# 19_SOLENOID_HB_1.net
KiCad netlist of a schematic drawn in Altium Designer
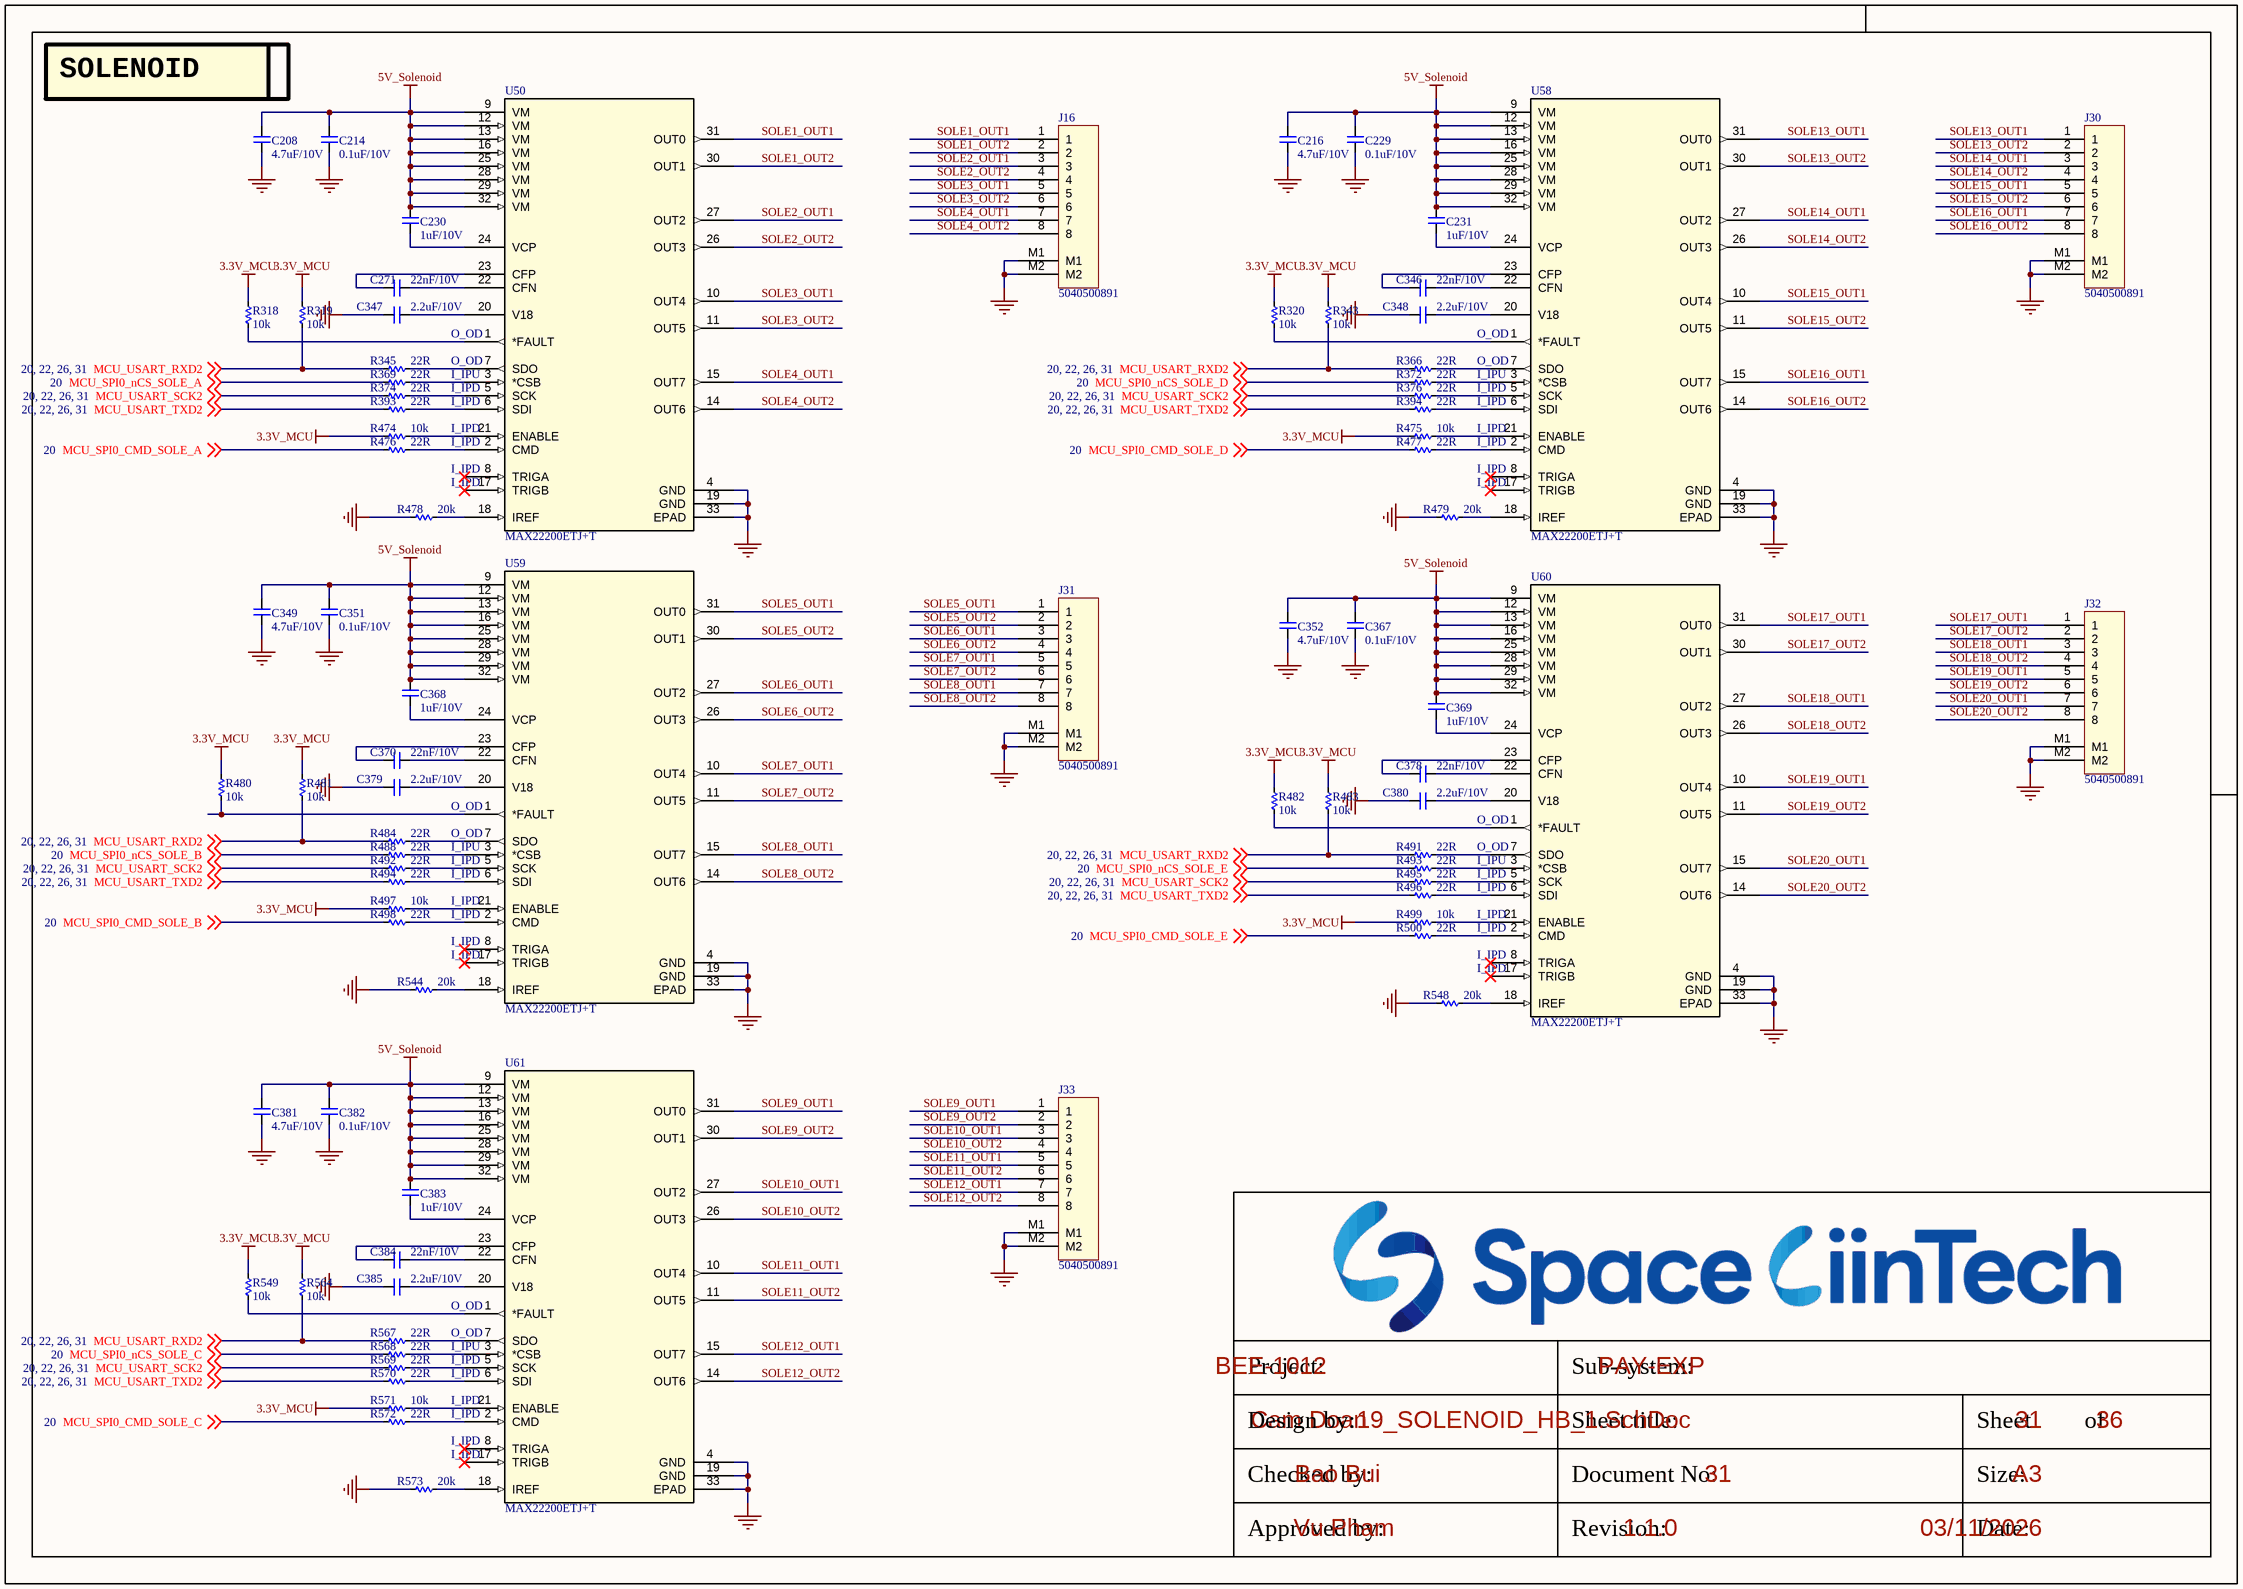
[diagram p0: 19_SOLENOID_HB_1.SchDoc]

(export (version "E")
  (design (tool "Eeschema 10.0.6"))
  (components
    (comp (ref "C208")
      (value "4.7uF/10V")
      (footprint "CAP_C_1005X60")
      (description "CAP CHIP")
      (libsource (lib "LABLIB") (part "_CAP_C_2"))
    )
    (comp (ref "C214")
      (value "0.1uF/10V")
      (footprint "CAP_C_1005X60")
      (description "CAP CHIP")
      (libsource (lib "LABLIB") (part "_CAP_C_2"))
    )
    (comp (ref "C216")
      (value "4.7uF/10V")
      (footprint "CAP_C_1005X60")
      (description "CAP CHIP")
      (libsource (lib "LABLIB") (part "_CAP_C_2"))
    )
    (comp (ref "C229")
      (value "0.1uF/10V")
      (footprint "CAP_C_1005X60")
      (description "CAP CHIP")
      (libsource (lib "LABLIB") (part "_CAP_C_2"))
    )
    (comp (ref "C230")
      (value "1uF/10V")
      (footprint "CAP_C_1005X60")
      (description "CAP CHIP")
      (libsource (lib "LABLIB") (part "_CAP_C_2"))
    )
    (comp (ref "C231")
      (value "1uF/10V")
      (footprint "CAP_C_1005X60")
      (description "CAP CHIP")
      (libsource (lib "LABLIB") (part "_CAP_C_2"))
    )
    (comp (ref "C271")
      (value "22nF/10V")
      (footprint "CAP_C_1005X60")
      (description "CAP CHIP")
      (libsource (lib "LABLIB") (part "_CAP_C_2"))
    )
    (comp (ref "C346")
      (value "22nF/10V")
      (footprint "CAP_C_1005X60")
      (description "CAP CHIP")
      (libsource (lib "LABLIB") (part "_CAP_C_2"))
    )
    (comp (ref "C347")
      (value "2.2uF/10V")
      (footprint "CAP_C_1005X60")
      (description "CAP CHIP")
      (libsource (lib "LABLIB") (part "_CAP_C_2"))
    )
    (comp (ref "C348")
      (value "2.2uF/10V")
      (footprint "CAP_C_1005X60")
      (description "CAP CHIP")
      (libsource (lib "LABLIB") (part "_CAP_C_2"))
    )
    (comp (ref "C349")
      (value "4.7uF/10V")
      (footprint "CAP_C_1005X60")
      (description "CAP CHIP")
      (libsource (lib "LABLIB") (part "_CAP_C_2"))
    )
    (comp (ref "C351")
      (value "0.1uF/10V")
      (footprint "CAP_C_1005X60")
      (description "CAP CHIP")
      (libsource (lib "LABLIB") (part "_CAP_C_2"))
    )
    (comp (ref "C352")
      (value "4.7uF/10V")
      (footprint "CAP_C_1005X60")
      (description "CAP CHIP")
      (libsource (lib "LABLIB") (part "_CAP_C_2"))
    )
    (comp (ref "C367")
      (value "0.1uF/10V")
      (footprint "CAP_C_1005X60")
      (description "CAP CHIP")
      (libsource (lib "LABLIB") (part "_CAP_C_2"))
    )
    (comp (ref "C368")
      (value "1uF/10V")
      (footprint "CAP_C_1005X60")
      (description "CAP CHIP")
      (libsource (lib "LABLIB") (part "_CAP_C_2"))
    )
    (comp (ref "C369")
      (value "1uF/10V")
      (footprint "CAP_C_1005X60")
      (description "CAP CHIP")
      (libsource (lib "LABLIB") (part "_CAP_C_2"))
    )
    (comp (ref "C370")
      (value "22nF/10V")
      (footprint "CAP_C_1005X60")
      (description "CAP CHIP")
      (libsource (lib "LABLIB") (part "_CAP_C_2"))
    )
    (comp (ref "C378")
      (value "22nF/10V")
      (footprint "CAP_C_1005X60")
      (description "CAP CHIP")
      (libsource (lib "LABLIB") (part "_CAP_C_2"))
    )
    (comp (ref "C379")
      (value "2.2uF/10V")
      (footprint "CAP_C_1005X60")
      (description "CAP CHIP")
      (libsource (lib "LABLIB") (part "_CAP_C_2"))
    )
    (comp (ref "C380")
      (value "2.2uF/10V")
      (footprint "CAP_C_1005X60")
      (description "CAP CHIP")
      (libsource (lib "LABLIB") (part "_CAP_C_2"))
    )
    (comp (ref "C381")
      (value "4.7uF/10V")
      (footprint "CAP_C_1005X60")
      (description "CAP CHIP")
      (libsource (lib "LABLIB") (part "_CAP_C_2"))
    )
    (comp (ref "C382")
      (value "0.1uF/10V")
      (footprint "CAP_C_1005X60")
      (description "CAP CHIP")
      (libsource (lib "LABLIB") (part "_CAP_C_2"))
    )
    (comp (ref "C383")
      (value "1uF/10V")
      (footprint "CAP_C_1005X60")
      (description "CAP CHIP")
      (libsource (lib "LABLIB") (part "_CAP_C_2"))
    )
    (comp (ref "C384")
      (value "22nF/10V")
      (footprint "CAP_C_1005X60")
      (description "CAP CHIP")
      (libsource (lib "LABLIB") (part "_CAP_C_2"))
    )
    (comp (ref "C385")
      (value "2.2uF/10V")
      (footprint "CAP_C_1005X60")
      (description "CAP CHIP")
      (libsource (lib "LABLIB") (part "_CAP_C_2"))
    )
    (comp (ref "J16")
      (value "5040500891")
      (footprint "MOLEX_5040500891")
      (libsource (lib "LABLIB") (part "Header 8x1_2M"))
    )
    (comp (ref "J30")
      (value "5040500891")
      (footprint "MOLEX_5040500891")
      (libsource (lib "LABLIB") (part "Header 8x1_2M"))
    )
    (comp (ref "J31")
      (value "5040500891")
      (footprint "MOLEX_5040500891")
      (libsource (lib "LABLIB") (part "Header 8x1_2M"))
    )
    (comp (ref "J32")
      (value "5040500891")
      (footprint "MOLEX_5040500891")
      (libsource (lib "LABLIB") (part "Header 8x1_2M"))
    )
    (comp (ref "J33")
      (value "5040500891")
      (footprint "MOLEX_5040500891")
      (libsource (lib "LABLIB") (part "Header 8x1_2M"))
    )
    (comp (ref "R318")
      (value "10k")
      (footprint "RES_C_1005X40")
      (description "RES")
      (libsource (lib "LABLIB") (part "_RES_B_2"))
    )
    (comp (ref "R319")
      (value "10k")
      (footprint "RES_C_1005X40")
      (description "RES")
      (libsource (lib "LABLIB") (part "_RES_B_2"))
    )
    (comp (ref "R320")
      (value "10k")
      (footprint "RES_C_1005X40")
      (description "RES")
      (libsource (lib "LABLIB") (part "_RES_B_2"))
    )
    (comp (ref "R343")
      (value "10k")
      (footprint "RES_C_1005X40")
      (description "RES")
      (libsource (lib "LABLIB") (part "_RES_B_2"))
    )
    (comp (ref "R345")
      (value "22R")
      (footprint "RES_C_1005X40")
      (description "RES")
      (libsource (lib "LABLIB") (part "_RES_B_2"))
    )
    (comp (ref "R366")
      (value "22R")
      (footprint "RES_C_1005X40")
      (description "RES")
      (libsource (lib "LABLIB") (part "_RES_B_2"))
    )
    (comp (ref "R369")
      (value "22R")
      (footprint "RES_C_1005X40")
      (description "RES")
      (libsource (lib "LABLIB") (part "_RES_B_2"))
    )
    (comp (ref "R372")
      (value "22R")
      (footprint "RES_C_1005X40")
      (description "RES")
      (libsource (lib "LABLIB") (part "_RES_B_2"))
    )
    (comp (ref "R374")
      (value "22R")
      (footprint "RES_C_1005X40")
      (description "RES")
      (libsource (lib "LABLIB") (part "_RES_B_2"))
    )
    (comp (ref "R376")
      (value "22R")
      (footprint "RES_C_1005X40")
      (description "RES")
      (libsource (lib "LABLIB") (part "_RES_B_2"))
    )
    (comp (ref "R393")
      (value "22R")
      (footprint "RES_C_1005X40")
      (description "RES")
      (libsource (lib "LABLIB") (part "_RES_B_2"))
    )
    (comp (ref "R394")
      (value "22R")
      (footprint "RES_C_1005X40")
      (description "RES")
      (libsource (lib "LABLIB") (part "_RES_B_2"))
    )
    (comp (ref "R474")
      (value "10k")
      (footprint "RES_C_1005X40")
      (description "RES")
      (libsource (lib "LABLIB") (part "_RES_B_2"))
    )
    (comp (ref "R475")
      (value "10k")
      (footprint "RES_C_1005X40")
      (description "RES")
      (libsource (lib "LABLIB") (part "_RES_B_2"))
    )
    (comp (ref "R476")
      (value "22R")
      (footprint "RES_C_1005X40")
      (description "RES")
      (libsource (lib "LABLIB") (part "_RES_B_2"))
    )
    (comp (ref "R477")
      (value "22R")
      (footprint "RES_C_1005X40")
      (description "RES")
      (libsource (lib "LABLIB") (part "_RES_B_2"))
    )
    (comp (ref "R478")
      (value "20k")
      (footprint "RES_C_1005X40")
      (description "RES")
      (libsource (lib "LABLIB") (part "_RES_B_2"))
    )
    (comp (ref "R479")
      (value "20k")
      (footprint "RES_C_1005X40")
      (description "RES")
      (libsource (lib "LABLIB") (part "_RES_B_2"))
    )
    (comp (ref "R480")
      (value "10k")
      (footprint "RES_C_1005X40")
      (description "RES")
      (libsource (lib "LABLIB") (part "_RES_B_2"))
    )
    (comp (ref "R481")
      (value "10k")
      (footprint "RES_C_1005X40")
      (description "RES")
      (libsource (lib "LABLIB") (part "_RES_B_2"))
    )
    (comp (ref "R482")
      (value "10k")
      (footprint "RES_C_1005X40")
      (description "RES")
      (libsource (lib "LABLIB") (part "_RES_B_2"))
    )
    (comp (ref "R483")
      (value "10k")
      (footprint "RES_C_1005X40")
      (description "RES")
      (libsource (lib "LABLIB") (part "_RES_B_2"))
    )
    (comp (ref "R484")
      (value "22R")
      (footprint "RES_C_1005X40")
      (description "RES")
      (libsource (lib "LABLIB") (part "_RES_B_2"))
    )
    (comp (ref "R488")
      (value "22R")
      (footprint "RES_C_1005X40")
      (description "RES")
      (libsource (lib "LABLIB") (part "_RES_B_2"))
    )
    (comp (ref "R491")
      (value "22R")
      (footprint "RES_C_1005X40")
      (description "RES")
      (libsource (lib "LABLIB") (part "_RES_B_2"))
    )
    (comp (ref "R492")
      (value "22R")
      (footprint "RES_C_1005X40")
      (description "RES")
      (libsource (lib "LABLIB") (part "_RES_B_2"))
    )
    (comp (ref "R493")
      (value "22R")
      (footprint "RES_C_1005X40")
      (description "RES")
      (libsource (lib "LABLIB") (part "_RES_B_2"))
    )
    (comp (ref "R494")
      (value "22R")
      (footprint "RES_C_1005X40")
      (description "RES")
      (libsource (lib "LABLIB") (part "_RES_B_2"))
    )
    (comp (ref "R495")
      (value "22R")
      (footprint "RES_C_1005X40")
      (description "RES")
      (libsource (lib "LABLIB") (part "_RES_B_2"))
    )
    (comp (ref "R496")
      (value "22R")
      (footprint "RES_C_1005X40")
      (description "RES")
      (libsource (lib "LABLIB") (part "_RES_B_2"))
    )
    (comp (ref "R497")
      (value "10k")
      (footprint "RES_C_1005X40")
      (description "RES")
      (libsource (lib "LABLIB") (part "_RES_B_2"))
    )
    (comp (ref "R498")
      (value "22R")
      (footprint "RES_C_1005X40")
      (description "RES")
      (libsource (lib "LABLIB") (part "_RES_B_2"))
    )
    (comp (ref "R499")
      (value "10k")
      (footprint "RES_C_1005X40")
      (description "RES")
      (libsource (lib "LABLIB") (part "_RES_B_2"))
    )
    (comp (ref "R500")
      (value "22R")
      (footprint "RES_C_1005X40")
      (description "RES")
      (libsource (lib "LABLIB") (part "_RES_B_2"))
    )
    (comp (ref "R544")
      (value "20k")
      (footprint "RES_C_1005X40")
      (description "RES")
      (libsource (lib "LABLIB") (part "_RES_B_2"))
    )
    (comp (ref "R548")
      (value "20k")
      (footprint "RES_C_1005X40")
      (description "RES")
      (libsource (lib "LABLIB") (part "_RES_B_2"))
    )
    (comp (ref "R549")
      (value "10k")
      (footprint "RES_C_1005X40")
      (description "RES")
      (libsource (lib "LABLIB") (part "_RES_B_2"))
    )
    (comp (ref "R564")
      (value "10k")
      (footprint "RES_C_1005X40")
      (description "RES")
      (libsource (lib "LABLIB") (part "_RES_B_2"))
    )
    (comp (ref "R567")
      (value "22R")
      (footprint "RES_C_1005X40")
      (description "RES")
      (libsource (lib "LABLIB") (part "_RES_B_2"))
    )
    (comp (ref "R568")
      (value "22R")
      (footprint "RES_C_1005X40")
      (description "RES")
      (libsource (lib "LABLIB") (part "_RES_B_2"))
    )
    (comp (ref "R569")
      (value "22R")
      (footprint "RES_C_1005X40")
      (description "RES")
      (libsource (lib "LABLIB") (part "_RES_B_2"))
    )
    (comp (ref "R570")
      (value "22R")
      (footprint "RES_C_1005X40")
      (description "RES")
      (libsource (lib "LABLIB") (part "_RES_B_2"))
    )
    (comp (ref "R571")
      (value "10k")
      (footprint "RES_C_1005X40")
      (description "RES")
      (libsource (lib "LABLIB") (part "_RES_B_2"))
    )
    (comp (ref "R572")
      (value "22R")
      (footprint "RES_C_1005X40")
      (description "RES")
      (libsource (lib "LABLIB") (part "_RES_B_2"))
    )
    (comp (ref "R573")
      (value "20k")
      (footprint "RES_C_1005X40")
      (description "RES")
      (libsource (lib "LABLIB") (part "_RES_B_2"))
    )
    (comp (ref "U50")
      (value "MAX22200ETJ+T")
      (footprint "21-0140AK_T3255_8C_MXM")
      (description "36V, 1A Octal Integrated Serial-Controlled Solenoid and Motor Driver")
      (fields (field (name "COPYRIGHT") "Copyright (C) 2026 Ultra Librarian. All rights reserved."))
      (libsource (lib "LABLIB") (part "MAX22200ETJ+T"))
    )
    (comp (ref "U58")
      (value "MAX22200ETJ+T")
      (footprint "21-0140AK_T3255_8C_MXM")
      (description "36V, 1A Octal Integrated Serial-Controlled Solenoid and Motor Driver")
      (fields (field (name "COPYRIGHT") "Copyright (C) 2026 Ultra Librarian. All rights reserved."))
      (libsource (lib "LABLIB") (part "MAX22200ETJ+T"))
    )
    (comp (ref "U59")
      (value "MAX22200ETJ+T")
      (footprint "21-0140AK_T3255_8C_MXM")
      (description "36V, 1A Octal Integrated Serial-Controlled Solenoid and Motor Driver")
      (fields (field (name "COPYRIGHT") "Copyright (C) 2026 Ultra Librarian. All rights reserved."))
      (libsource (lib "LABLIB") (part "MAX22200ETJ+T"))
    )
    (comp (ref "U60")
      (value "MAX22200ETJ+T")
      (footprint "21-0140AK_T3255_8C_MXM")
      (description "36V, 1A Octal Integrated Serial-Controlled Solenoid and Motor Driver")
      (fields (field (name "COPYRIGHT") "Copyright (C) 2026 Ultra Librarian. All rights reserved."))
      (libsource (lib "LABLIB") (part "MAX22200ETJ+T"))
    )
    (comp (ref "U61")
      (value "MAX22200ETJ+T")
      (footprint "21-0140AK_T3255_8C_MXM")
      (description "36V, 1A Octal Integrated Serial-Controlled Solenoid and Motor Driver")
      (fields (field (name "COPYRIGHT") "Copyright (C) 2026 Ultra Librarian. All rights reserved."))
      (libsource (lib "LABLIB") (part "MAX22200ETJ+T"))
    )
  )
  (nets
    (net (code "1") (name "/SOLE1_OUT1") (class "Default")
      (node (ref "J16") (pin "1") (pinfunction "1_1") (pintype "passive"))
      (node (ref "U50") (pin "31") (pinfunction "OUT0_31") (pintype "output"))
    )
    (net (code "2") (name "/SOLE1_OUT2") (class "Default")
      (node (ref "J16") (pin "2") (pinfunction "2_2") (pintype "passive"))
      (node (ref "U50") (pin "30") (pinfunction "OUT1_30") (pintype "output"))
    )
    (net (code "3") (name "/SOLE2_OUT1") (class "Default")
      (node (ref "J16") (pin "3") (pinfunction "3_3") (pintype "passive"))
      (node (ref "U50") (pin "27") (pinfunction "OUT2_27") (pintype "output"))
    )
    (net (code "4") (name "/SOLE2_OUT2") (class "Default")
      (node (ref "J16") (pin "4") (pinfunction "4_4") (pintype "passive"))
      (node (ref "U50") (pin "26") (pinfunction "OUT3_26") (pintype "output"))
    )
    (net (code "5") (name "/SOLE3_OUT1") (class "Default")
      (node (ref "J16") (pin "5") (pinfunction "5_5") (pintype "passive"))
      (node (ref "U50") (pin "10") (pinfunction "OUT4_10") (pintype "output"))
    )
    (net (code "6") (name "/SOLE3_OUT2") (class "Default")
      (node (ref "J16") (pin "6") (pinfunction "6_6") (pintype "passive"))
      (node (ref "U50") (pin "11") (pinfunction "OUT5_11") (pintype "output"))
    )
    (net (code "7") (name "/SOLE4_OUT1") (class "Default")
      (node (ref "J16") (pin "7") (pinfunction "7_7") (pintype "passive"))
      (node (ref "U50") (pin "15") (pinfunction "OUT7_15") (pintype "output"))
    )
    (net (code "8") (name "/SOLE4_OUT2") (class "Default")
      (node (ref "J16") (pin "8") (pinfunction "8_8") (pintype "passive"))
      (node (ref "U50") (pin "14") (pinfunction "OUT6_14") (pintype "output"))
    )
    (net (code "9") (name "/SOLE5_OUT1") (class "Default")
      (node (ref "J31") (pin "1") (pinfunction "1_1") (pintype "passive"))
      (node (ref "U59") (pin "31") (pinfunction "OUT0_31") (pintype "output"))
    )
    (net (code "10") (name "/SOLE5_OUT2") (class "Default")
      (node (ref "J31") (pin "2") (pinfunction "2_2") (pintype "passive"))
      (node (ref "U59") (pin "30") (pinfunction "OUT1_30") (pintype "output"))
    )
    (net (code "11") (name "/SOLE6_OUT1") (class "Default")
      (node (ref "J31") (pin "3") (pinfunction "3_3") (pintype "passive"))
      (node (ref "U59") (pin "27") (pinfunction "OUT2_27") (pintype "output"))
    )
    (net (code "12") (name "/SOLE6_OUT2") (class "Default")
      (node (ref "J31") (pin "4") (pinfunction "4_4") (pintype "passive"))
      (node (ref "U59") (pin "26") (pinfunction "OUT3_26") (pintype "output"))
    )
    (net (code "13") (name "/SOLE7_OUT1") (class "Default")
      (node (ref "J31") (pin "5") (pinfunction "5_5") (pintype "passive"))
      (node (ref "U59") (pin "10") (pinfunction "OUT4_10") (pintype "output"))
    )
    (net (code "14") (name "/SOLE7_OUT2") (class "Default")
      (node (ref "J31") (pin "6") (pinfunction "6_6") (pintype "passive"))
      (node (ref "U59") (pin "11") (pinfunction "OUT5_11") (pintype "output"))
    )
    (net (code "15") (name "/SOLE8_OUT1") (class "Default")
      (node (ref "J31") (pin "7") (pinfunction "7_7") (pintype "passive"))
      (node (ref "U59") (pin "15") (pinfunction "OUT7_15") (pintype "output"))
    )
    (net (code "16") (name "/SOLE8_OUT2") (class "Default")
      (node (ref "J31") (pin "8") (pinfunction "8_8") (pintype "passive"))
      (node (ref "U59") (pin "14") (pinfunction "OUT6_14") (pintype "output"))
    )
    (net (code "17") (name "/SOLE9_OUT1") (class "Default")
      (node (ref "J33") (pin "1") (pinfunction "1_1") (pintype "passive"))
      (node (ref "U61") (pin "31") (pinfunction "OUT0_31") (pintype "output"))
    )
    (net (code "18") (name "/SOLE9_OUT2") (class "Default")
      (node (ref "J33") (pin "2") (pinfunction "2_2") (pintype "passive"))
      (node (ref "U61") (pin "30") (pinfunction "OUT1_30") (pintype "output"))
    )
    (net (code "19") (name "/SOLE10_OUT1") (class "Default")
      (node (ref "J33") (pin "3") (pinfunction "3_3") (pintype "passive"))
      (node (ref "U61") (pin "27") (pinfunction "OUT2_27") (pintype "output"))
    )
    (net (code "20") (name "/SOLE10_OUT2") (class "Default")
      (node (ref "J33") (pin "4") (pinfunction "4_4") (pintype "passive"))
      (node (ref "U61") (pin "26") (pinfunction "OUT3_26") (pintype "output"))
    )
    (net (code "21") (name "/SOLE11_OUT1") (class "Default")
      (node (ref "J33") (pin "5") (pinfunction "5_5") (pintype "passive"))
      (node (ref "U61") (pin "10") (pinfunction "OUT4_10") (pintype "output"))
    )
    (net (code "22") (name "/SOLE11_OUT2") (class "Default")
      (node (ref "J33") (pin "6") (pinfunction "6_6") (pintype "passive"))
      (node (ref "U61") (pin "11") (pinfunction "OUT5_11") (pintype "output"))
    )
    (net (code "23") (name "/SOLE12_OUT1") (class "Default")
      (node (ref "J33") (pin "7") (pinfunction "7_7") (pintype "passive"))
      (node (ref "U61") (pin "15") (pinfunction "OUT7_15") (pintype "output"))
    )
    (net (code "24") (name "/SOLE12_OUT2") (class "Default")
      (node (ref "J33") (pin "8") (pinfunction "8_8") (pintype "passive"))
      (node (ref "U61") (pin "14") (pinfunction "OUT6_14") (pintype "output"))
    )
    (net (code "25") (name "/SOLE13_OUT1") (class "Default")
      (node (ref "J30") (pin "1") (pinfunction "1_1") (pintype "passive"))
      (node (ref "U58") (pin "31") (pinfunction "OUT0_31") (pintype "output"))
    )
    (net (code "26") (name "/SOLE13_OUT2") (class "Default")
      (node (ref "J30") (pin "2") (pinfunction "2_2") (pintype "passive"))
      (node (ref "U58") (pin "30") (pinfunction "OUT1_30") (pintype "output"))
    )
    (net (code "27") (name "/SOLE14_OUT1") (class "Default")
      (node (ref "J30") (pin "3") (pinfunction "3_3") (pintype "passive"))
      (node (ref "U58") (pin "27") (pinfunction "OUT2_27") (pintype "output"))
    )
    (net (code "28") (name "/SOLE14_OUT2") (class "Default")
      (node (ref "J30") (pin "4") (pinfunction "4_4") (pintype "passive"))
      (node (ref "U58") (pin "26") (pinfunction "OUT3_26") (pintype "output"))
    )
    (net (code "29") (name "/SOLE15_OUT1") (class "Default")
      (node (ref "J30") (pin "5") (pinfunction "5_5") (pintype "passive"))
      (node (ref "U58") (pin "10") (pinfunction "OUT4_10") (pintype "output"))
    )
    (net (code "30") (name "/SOLE15_OUT2") (class "Default")
      (node (ref "J30") (pin "6") (pinfunction "6_6") (pintype "passive"))
      (node (ref "U58") (pin "11") (pinfunction "OUT5_11") (pintype "output"))
    )
    (net (code "31") (name "/SOLE16_OUT1") (class "Default")
      (node (ref "J30") (pin "7") (pinfunction "7_7") (pintype "passive"))
      (node (ref "U58") (pin "15") (pinfunction "OUT7_15") (pintype "output"))
    )
    (net (code "32") (name "/SOLE16_OUT2") (class "Default")
      (node (ref "J30") (pin "8") (pinfunction "8_8") (pintype "passive"))
      (node (ref "U58") (pin "14") (pinfunction "OUT6_14") (pintype "output"))
    )
    (net (code "33") (name "/SOLE17_OUT1") (class "Default")
      (node (ref "J32") (pin "1") (pinfunction "1_1") (pintype "passive"))
      (node (ref "U60") (pin "31") (pinfunction "OUT0_31") (pintype "output"))
    )
    (net (code "34") (name "/SOLE17_OUT2") (class "Default")
      (node (ref "J32") (pin "2") (pinfunction "2_2") (pintype "passive"))
      (node (ref "U60") (pin "30") (pinfunction "OUT1_30") (pintype "output"))
    )
    (net (code "35") (name "/SOLE18_OUT1") (class "Default")
      (node (ref "J32") (pin "3") (pinfunction "3_3") (pintype "passive"))
      (node (ref "U60") (pin "27") (pinfunction "OUT2_27") (pintype "output"))
    )
    (net (code "36") (name "/SOLE18_OUT2") (class "Default")
      (node (ref "J32") (pin "4") (pinfunction "4_4") (pintype "passive"))
      (node (ref "U60") (pin "26") (pinfunction "OUT3_26") (pintype "output"))
    )
    (net (code "37") (name "/SOLE19_OUT1") (class "Default")
      (node (ref "J32") (pin "5") (pinfunction "5_5") (pintype "passive"))
      (node (ref "U60") (pin "10") (pinfunction "OUT4_10") (pintype "output"))
    )
    (net (code "38") (name "/SOLE19_OUT2") (class "Default")
      (node (ref "J32") (pin "6") (pinfunction "6_6") (pintype "passive"))
      (node (ref "U60") (pin "11") (pinfunction "OUT5_11") (pintype "output"))
    )
    (net (code "39") (name "/SOLE20_OUT1") (class "Default")
      (node (ref "J32") (pin "7") (pinfunction "7_7") (pintype "passive"))
      (node (ref "U60") (pin "15") (pinfunction "OUT7_15") (pintype "output"))
    )
    (net (code "40") (name "/SOLE20_OUT2") (class "Default")
      (node (ref "J32") (pin "8") (pinfunction "8_8") (pintype "passive"))
      (node (ref "U60") (pin "14") (pinfunction "OUT6_14") (pintype "output"))
    )
    (net (code "41") (name "3.3V_MCU") (class "Default")
      (node (ref "R318") (pin "1") (pinfunction "1_1") (pintype "passive"))
      (node (ref "R319") (pin "1") (pinfunction "1_1") (pintype "passive"))
      (node (ref "R320") (pin "1") (pinfunction "1_1") (pintype "passive"))
      (node (ref "R343") (pin "1") (pinfunction "1_1") (pintype "passive"))
      (node (ref "R474") (pin "1") (pinfunction "1_1") (pintype "passive"))
      (node (ref "R475") (pin "1") (pinfunction "1_1") (pintype "passive"))
      (node (ref "R480") (pin "1") (pinfunction "1_1") (pintype "passive"))
      (node (ref "R481") (pin "1") (pinfunction "1_1") (pintype "passive"))
      (node (ref "R482") (pin "1") (pinfunction "1_1") (pintype "passive"))
      (node (ref "R483") (pin "1") (pinfunction "1_1") (pintype "passive"))
      (node (ref "R497") (pin "1") (pinfunction "1_1") (pintype "passive"))
      (node (ref "R499") (pin "1") (pinfunction "1_1") (pintype "passive"))
      (node (ref "R549") (pin "1") (pinfunction "1_1") (pintype "passive"))
      (node (ref "R564") (pin "1") (pinfunction "1_1") (pintype "passive"))
      (node (ref "R571") (pin "1") (pinfunction "1_1") (pintype "passive"))
    )
    (net (code "42") (name "5V_Solenoid") (class "Default")
      (node (ref "C208") (pin "2") (pinfunction "2_2") (pintype "passive"))
      (node (ref "C214") (pin "2") (pinfunction "2_2") (pintype "passive"))
      (node (ref "C216") (pin "2") (pinfunction "2_2") (pintype "passive"))
      (node (ref "C229") (pin "2") (pinfunction "2_2") (pintype "passive"))
      (node (ref "C230") (pin "2") (pinfunction "2_2") (pintype "passive"))
      (node (ref "C231") (pin "2") (pinfunction "2_2") (pintype "passive"))
      (node (ref "C349") (pin "2") (pinfunction "2_2") (pintype "passive"))
      (node (ref "C351") (pin "2") (pinfunction "2_2") (pintype "passive"))
      (node (ref "C352") (pin "2") (pinfunction "2_2") (pintype "passive"))
      (node (ref "C367") (pin "2") (pinfunction "2_2") (pintype "passive"))
      (node (ref "C368") (pin "2") (pinfunction "2_2") (pintype "passive"))
      (node (ref "C369") (pin "2") (pinfunction "2_2") (pintype "passive"))
      (node (ref "C381") (pin "2") (pinfunction "2_2") (pintype "passive"))
      (node (ref "C382") (pin "2") (pinfunction "2_2") (pintype "passive"))
      (node (ref "C383") (pin "2") (pinfunction "2_2") (pintype "passive"))
      (node (ref "U50") (pin "12") (pinfunction "VM_12") (pintype "input"))
      (node (ref "U50") (pin "13") (pinfunction "VM_13") (pintype "input"))
      (node (ref "U50") (pin "16") (pinfunction "VM_16") (pintype "input"))
      (node (ref "U50") (pin "25") (pinfunction "VM_25") (pintype "input"))
      (node (ref "U50") (pin "28") (pinfunction "VM_28") (pintype "input"))
      (node (ref "U50") (pin "29") (pinfunction "VM_29") (pintype "input"))
      (node (ref "U50") (pin "32") (pinfunction "VM_32") (pintype "input"))
      (node (ref "U50") (pin "9") (pinfunction "VM_9") (pintype "power_in"))
      (node (ref "U58") (pin "12") (pinfunction "VM_12") (pintype "input"))
      (node (ref "U58") (pin "13") (pinfunction "VM_13") (pintype "input"))
      (node (ref "U58") (pin "16") (pinfunction "VM_16") (pintype "input"))
      (node (ref "U58") (pin "25") (pinfunction "VM_25") (pintype "input"))
      (node (ref "U58") (pin "28") (pinfunction "VM_28") (pintype "input"))
      (node (ref "U58") (pin "29") (pinfunction "VM_29") (pintype "input"))
      (node (ref "U58") (pin "32") (pinfunction "VM_32") (pintype "input"))
      (node (ref "U58") (pin "9") (pinfunction "VM_9") (pintype "power_in"))
      (node (ref "U59") (pin "12") (pinfunction "VM_12") (pintype "input"))
      (node (ref "U59") (pin "13") (pinfunction "VM_13") (pintype "input"))
      (node (ref "U59") (pin "16") (pinfunction "VM_16") (pintype "input"))
      (node (ref "U59") (pin "25") (pinfunction "VM_25") (pintype "input"))
      (node (ref "U59") (pin "28") (pinfunction "VM_28") (pintype "input"))
      (node (ref "U59") (pin "29") (pinfunction "VM_29") (pintype "input"))
      (node (ref "U59") (pin "32") (pinfunction "VM_32") (pintype "input"))
      (node (ref "U59") (pin "9") (pinfunction "VM_9") (pintype "power_in"))
      (node (ref "U60") (pin "12") (pinfunction "VM_12") (pintype "input"))
      (node (ref "U60") (pin "13") (pinfunction "VM_13") (pintype "input"))
      (node (ref "U60") (pin "16") (pinfunction "VM_16") (pintype "input"))
      (node (ref "U60") (pin "25") (pinfunction "VM_25") (pintype "input"))
      (node (ref "U60") (pin "28") (pinfunction "VM_28") (pintype "input"))
      (node (ref "U60") (pin "29") (pinfunction "VM_29") (pintype "input"))
      (node (ref "U60") (pin "32") (pinfunction "VM_32") (pintype "input"))
      (node (ref "U60") (pin "9") (pinfunction "VM_9") (pintype "power_in"))
      (node (ref "U61") (pin "12") (pinfunction "VM_12") (pintype "input"))
      (node (ref "U61") (pin "13") (pinfunction "VM_13") (pintype "input"))
      (node (ref "U61") (pin "16") (pinfunction "VM_16") (pintype "input"))
      (node (ref "U61") (pin "25") (pinfunction "VM_25") (pintype "input"))
      (node (ref "U61") (pin "28") (pinfunction "VM_28") (pintype "input"))
      (node (ref "U61") (pin "29") (pinfunction "VM_29") (pintype "input"))
      (node (ref "U61") (pin "32") (pinfunction "VM_32") (pintype "input"))
      (node (ref "U61") (pin "9") (pinfunction "VM_9") (pintype "power_in"))
    )
    (net (code "43") (name "GND") (class "Default")
      (node (ref "C208") (pin "1") (pinfunction "1_1") (pintype "passive"))
      (node (ref "C214") (pin "1") (pinfunction "1_1") (pintype "passive"))
      (node (ref "C216") (pin "1") (pinfunction "1_1") (pintype "passive"))
      (node (ref "C229") (pin "1") (pinfunction "1_1") (pintype "passive"))
      (node (ref "C347") (pin "1") (pinfunction "1_1") (pintype "passive"))
      (node (ref "C348") (pin "1") (pinfunction "1_1") (pintype "passive"))
      (node (ref "C349") (pin "1") (pinfunction "1_1") (pintype "passive"))
      (node (ref "C351") (pin "1") (pinfunction "1_1") (pintype "passive"))
      (node (ref "C352") (pin "1") (pinfunction "1_1") (pintype "passive"))
      (node (ref "C367") (pin "1") (pinfunction "1_1") (pintype "passive"))
      (node (ref "C379") (pin "1") (pinfunction "1_1") (pintype "passive"))
      (node (ref "C380") (pin "1") (pinfunction "1_1") (pintype "passive"))
      (node (ref "C381") (pin "1") (pinfunction "1_1") (pintype "passive"))
      (node (ref "C382") (pin "1") (pinfunction "1_1") (pintype "passive"))
      (node (ref "C385") (pin "1") (pinfunction "1_1") (pintype "passive"))
      (node (ref "J16") (pin "M1") (pinfunction "M1_M1") (pintype "passive"))
      (node (ref "J16") (pin "M2") (pinfunction "M2_M2") (pintype "passive"))
      (node (ref "J30") (pin "M1") (pinfunction "M1_M1") (pintype "passive"))
      (node (ref "J30") (pin "M2") (pinfunction "M2_M2") (pintype "passive"))
      (node (ref "J31") (pin "M1") (pinfunction "M1_M1") (pintype "passive"))
      (node (ref "J31") (pin "M2") (pinfunction "M2_M2") (pintype "passive"))
      (node (ref "J32") (pin "M1") (pinfunction "M1_M1") (pintype "passive"))
      (node (ref "J32") (pin "M2") (pinfunction "M2_M2") (pintype "passive"))
      (node (ref "J33") (pin "M1") (pinfunction "M1_M1") (pintype "passive"))
      (node (ref "J33") (pin "M2") (pinfunction "M2_M2") (pintype "passive"))
      (node (ref "R478") (pin "1") (pinfunction "1_1") (pintype "passive"))
      (node (ref "R479") (pin "1") (pinfunction "1_1") (pintype "passive"))
      (node (ref "R544") (pin "1") (pinfunction "1_1") (pintype "passive"))
      (node (ref "R548") (pin "1") (pinfunction "1_1") (pintype "passive"))
      (node (ref "R573") (pin "1") (pinfunction "1_1") (pintype "passive"))
      (node (ref "U50") (pin "19") (pinfunction "GND_19") (pintype "power_in"))
      (node (ref "U50") (pin "33") (pinfunction "EPAD_33") (pintype "power_in"))
      (node (ref "U50") (pin "4") (pinfunction "GND_4") (pintype "power_in"))
      (node (ref "U58") (pin "19") (pinfunction "GND_19") (pintype "power_in"))
      (node (ref "U58") (pin "33") (pinfunction "EPAD_33") (pintype "power_in"))
      (node (ref "U58") (pin "4") (pinfunction "GND_4") (pintype "power_in"))
      (node (ref "U59") (pin "19") (pinfunction "GND_19") (pintype "power_in"))
      (node (ref "U59") (pin "33") (pinfunction "EPAD_33") (pintype "power_in"))
      (node (ref "U59") (pin "4") (pinfunction "GND_4") (pintype "power_in"))
      (node (ref "U60") (pin "19") (pinfunction "GND_19") (pintype "power_in"))
      (node (ref "U60") (pin "33") (pinfunction "EPAD_33") (pintype "power_in"))
      (node (ref "U60") (pin "4") (pinfunction "GND_4") (pintype "power_in"))
      (node (ref "U61") (pin "19") (pinfunction "GND_19") (pintype "power_in"))
      (node (ref "U61") (pin "33") (pinfunction "EPAD_33") (pintype "power_in"))
      (node (ref "U61") (pin "4") (pinfunction "GND_4") (pintype "power_in"))
    )
    (net (code "44") (name "MCU_SPI0_CMD_SOLE_A") (class "Default")
      (node (ref "R476") (pin "1") (pinfunction "1_1") (pintype "passive"))
    )
    (net (code "45") (name "MCU_SPI0_CMD_SOLE_B") (class "Default")
      (node (ref "R498") (pin "1") (pinfunction "1_1") (pintype "passive"))
    )
    (net (code "46") (name "MCU_SPI0_CMD_SOLE_C") (class "Default")
      (node (ref "R572") (pin "1") (pinfunction "1_1") (pintype "passive"))
    )
    (net (code "47") (name "MCU_SPI0_CMD_SOLE_D") (class "Default")
      (node (ref "R477") (pin "1") (pinfunction "1_1") (pintype "passive"))
    )
    (net (code "48") (name "MCU_SPI0_CMD_SOLE_E") (class "Default")
      (node (ref "R500") (pin "1") (pinfunction "1_1") (pintype "passive"))
    )
    (net (code "49") (name "MCU_SPI0_nCS_SOLE_A") (class "Default")
      (node (ref "R369") (pin "1") (pinfunction "1_1") (pintype "passive"))
    )
    (net (code "50") (name "MCU_SPI0_nCS_SOLE_B") (class "Default")
      (node (ref "R488") (pin "1") (pinfunction "1_1") (pintype "passive"))
    )
    (net (code "51") (name "MCU_SPI0_nCS_SOLE_C") (class "Default")
      (node (ref "R568") (pin "1") (pinfunction "1_1") (pintype "passive"))
    )
    (net (code "52") (name "MCU_SPI0_nCS_SOLE_D") (class "Default")
      (node (ref "R372") (pin "1") (pinfunction "1_1") (pintype "passive"))
    )
    (net (code "53") (name "MCU_SPI0_nCS_SOLE_E") (class "Default")
      (node (ref "R493") (pin "1") (pinfunction "1_1") (pintype "passive"))
    )
    (net (code "54") (name "MCU_USART_RXD2") (class "Default")
      (node (ref "R319") (pin "2") (pinfunction "2_2") (pintype "passive"))
      (node (ref "R343") (pin "2") (pinfunction "2_2") (pintype "passive"))
      (node (ref "R345") (pin "1") (pinfunction "1_1") (pintype "passive"))
      (node (ref "R366") (pin "1") (pinfunction "1_1") (pintype "passive"))
      (node (ref "R481") (pin "2") (pinfunction "2_2") (pintype "passive"))
      (node (ref "R483") (pin "2") (pinfunction "2_2") (pintype "passive"))
      (node (ref "R484") (pin "1") (pinfunction "1_1") (pintype "passive"))
      (node (ref "R491") (pin "1") (pinfunction "1_1") (pintype "passive"))
      (node (ref "R564") (pin "2") (pinfunction "2_2") (pintype "passive"))
      (node (ref "R567") (pin "1") (pinfunction "1_1") (pintype "passive"))
    )
    (net (code "55") (name "MCU_USART_SCK2") (class "Default")
      (node (ref "R374") (pin "1") (pinfunction "1_1") (pintype "passive"))
      (node (ref "R376") (pin "1") (pinfunction "1_1") (pintype "passive"))
      (node (ref "R492") (pin "1") (pinfunction "1_1") (pintype "passive"))
      (node (ref "R495") (pin "1") (pinfunction "1_1") (pintype "passive"))
      (node (ref "R569") (pin "1") (pinfunction "1_1") (pintype "passive"))
    )
    (net (code "56") (name "MCU_USART_TXD2") (class "Default")
      (node (ref "R393") (pin "1") (pinfunction "1_1") (pintype "passive"))
      (node (ref "R394") (pin "1") (pinfunction "1_1") (pintype "passive"))
      (node (ref "R494") (pin "1") (pinfunction "1_1") (pintype "passive"))
      (node (ref "R496") (pin "1") (pinfunction "1_1") (pintype "passive"))
      (node (ref "R570") (pin "1") (pinfunction "1_1") (pintype "passive"))
    )
    (net (code "57") (name "Net-(U50-*CSB)") (class "Default")
      (node (ref "R369") (pin "2") (pinfunction "2_2") (pintype "passive"))
      (node (ref "U50") (pin "3") (pinfunction "*CSB_3") (pintype "input"))
    )
    (net (code "58") (name "Net-(U50-*FAULT)") (class "Default")
      (node (ref "R318") (pin "2") (pinfunction "2_2") (pintype "passive"))
      (node (ref "U50") (pin "1") (pinfunction "*FAULT_1") (pintype "output"))
    )
    (net (code "59") (name "Net-(U50-CFN)") (class "Default")
      (node (ref "C271") (pin "1") (pinfunction "1_1") (pintype "passive"))
      (node (ref "U50") (pin "22") (pinfunction "CFN_22") (pintype "power_in"))
    )
    (net (code "60") (name "Net-(U50-CFP)") (class "Default")
      (node (ref "C271") (pin "2") (pinfunction "2_2") (pintype "passive"))
      (node (ref "U50") (pin "23") (pinfunction "CFP_23") (pintype "power_in"))
    )
    (net (code "61") (name "Net-(U50-CMD)") (class "Default")
      (node (ref "R476") (pin "2") (pinfunction "2_2") (pintype "passive"))
      (node (ref "U50") (pin "2") (pinfunction "CMD_2") (pintype "input"))
    )
    (net (code "62") (name "Net-(U50-ENABLE)") (class "Default")
      (node (ref "R474") (pin "2") (pinfunction "2_2") (pintype "passive"))
      (node (ref "U50") (pin "21") (pinfunction "ENABLE_21") (pintype "input"))
    )
    (net (code "63") (name "Net-(U50-IREF)") (class "Default")
      (node (ref "R478") (pin "2") (pinfunction "2_2") (pintype "passive"))
      (node (ref "U50") (pin "18") (pinfunction "IREF_18") (pintype "input"))
    )
    (net (code "64") (name "Net-(U50-SCK)") (class "Default")
      (node (ref "R374") (pin "2") (pinfunction "2_2") (pintype "passive"))
      (node (ref "U50") (pin "5") (pinfunction "SCK_5") (pintype "input"))
    )
    (net (code "65") (name "Net-(U50-SDI)") (class "Default")
      (node (ref "R393") (pin "2") (pinfunction "2_2") (pintype "passive"))
      (node (ref "U50") (pin "6") (pinfunction "SDI_6") (pintype "input"))
    )
    (net (code "66") (name "Net-(U50-SDO)") (class "Default")
      (node (ref "R345") (pin "2") (pinfunction "2_2") (pintype "passive"))
      (node (ref "U50") (pin "7") (pinfunction "SDO_7") (pintype "output"))
    )
    (net (code "67") (name "Net-(U50-V18)") (class "Default")
      (node (ref "C347") (pin "2") (pinfunction "2_2") (pintype "passive"))
      (node (ref "U50") (pin "20") (pinfunction "V18_20") (pintype "power_in"))
    )
    (net (code "68") (name "Net-(U50-VCP)") (class "Default")
      (node (ref "C230") (pin "1") (pinfunction "1_1") (pintype "passive"))
      (node (ref "U50") (pin "24") (pinfunction "VCP_24") (pintype "power_in"))
    )
    (net (code "69") (name "Net-(U58-*CSB)") (class "Default")
      (node (ref "R372") (pin "2") (pinfunction "2_2") (pintype "passive"))
      (node (ref "U58") (pin "3") (pinfunction "*CSB_3") (pintype "input"))
    )
    (net (code "70") (name "Net-(U58-*FAULT)") (class "Default")
      (node (ref "R320") (pin "2") (pinfunction "2_2") (pintype "passive"))
      (node (ref "U58") (pin "1") (pinfunction "*FAULT_1") (pintype "output"))
    )
    (net (code "71") (name "Net-(U58-CFN)") (class "Default")
      (node (ref "C346") (pin "1") (pinfunction "1_1") (pintype "passive"))
      (node (ref "U58") (pin "22") (pinfunction "CFN_22") (pintype "power_in"))
    )
    (net (code "72") (name "Net-(U58-CFP)") (class "Default")
      (node (ref "C346") (pin "2") (pinfunction "2_2") (pintype "passive"))
      (node (ref "U58") (pin "23") (pinfunction "CFP_23") (pintype "power_in"))
    )
    (net (code "73") (name "Net-(U58-CMD)") (class "Default")
      (node (ref "R477") (pin "2") (pinfunction "2_2") (pintype "passive"))
      (node (ref "U58") (pin "2") (pinfunction "CMD_2") (pintype "input"))
    )
    (net (code "74") (name "Net-(U58-ENABLE)") (class "Default")
      (node (ref "R475") (pin "2") (pinfunction "2_2") (pintype "passive"))
      (node (ref "U58") (pin "21") (pinfunction "ENABLE_21") (pintype "input"))
    )
    (net (code "75") (name "Net-(U58-IREF)") (class "Default")
      (node (ref "R479") (pin "2") (pinfunction "2_2") (pintype "passive"))
      (node (ref "U58") (pin "18") (pinfunction "IREF_18") (pintype "input"))
    )
    (net (code "76") (name "Net-(U58-SCK)") (class "Default")
      (node (ref "R376") (pin "2") (pinfunction "2_2") (pintype "passive"))
      (node (ref "U58") (pin "5") (pinfunction "SCK_5") (pintype "input"))
    )
    (net (code "77") (name "Net-(U58-SDI)") (class "Default")
      (node (ref "R394") (pin "2") (pinfunction "2_2") (pintype "passive"))
      (node (ref "U58") (pin "6") (pinfunction "SDI_6") (pintype "input"))
    )
    (net (code "78") (name "Net-(U58-SDO)") (class "Default")
      (node (ref "R366") (pin "2") (pinfunction "2_2") (pintype "passive"))
      (node (ref "U58") (pin "7") (pinfunction "SDO_7") (pintype "output"))
    )
    (net (code "79") (name "Net-(U58-V18)") (class "Default")
      (node (ref "C348") (pin "2") (pinfunction "2_2") (pintype "passive"))
      (node (ref "U58") (pin "20") (pinfunction "V18_20") (pintype "power_in"))
    )
    (net (code "80") (name "Net-(U58-VCP)") (class "Default")
      (node (ref "C231") (pin "1") (pinfunction "1_1") (pintype "passive"))
      (node (ref "U58") (pin "24") (pinfunction "VCP_24") (pintype "power_in"))
    )
    (net (code "81") (name "Net-(U59-*CSB)") (class "Default")
      (node (ref "R488") (pin "2") (pinfunction "2_2") (pintype "passive"))
      (node (ref "U59") (pin "3") (pinfunction "*CSB_3") (pintype "input"))
    )
    (net (code "82") (name "Net-(U59-*FAULT)") (class "Default")
      (node (ref "R480") (pin "2") (pinfunction "2_2") (pintype "passive"))
      (node (ref "U59") (pin "1") (pinfunction "*FAULT_1") (pintype "output"))
    )
    (net (code "83") (name "Net-(U59-CFN)") (class "Default")
      (node (ref "C370") (pin "1") (pinfunction "1_1") (pintype "passive"))
      (node (ref "U59") (pin "22") (pinfunction "CFN_22") (pintype "power_in"))
    )
    (net (code "84") (name "Net-(U59-CFP)") (class "Default")
      (node (ref "C370") (pin "2") (pinfunction "2_2") (pintype "passive"))
      (node (ref "U59") (pin "23") (pinfunction "CFP_23") (pintype "power_in"))
    )
    (net (code "85") (name "Net-(U59-CMD)") (class "Default")
      (node (ref "R498") (pin "2") (pinfunction "2_2") (pintype "passive"))
      (node (ref "U59") (pin "2") (pinfunction "CMD_2") (pintype "input"))
    )
    (net (code "86") (name "Net-(U59-ENABLE)") (class "Default")
      (node (ref "R497") (pin "2") (pinfunction "2_2") (pintype "passive"))
      (node (ref "U59") (pin "21") (pinfunction "ENABLE_21") (pintype "input"))
    )
    (net (code "87") (name "Net-(U59-IREF)") (class "Default")
      (node (ref "R544") (pin "2") (pinfunction "2_2") (pintype "passive"))
      (node (ref "U59") (pin "18") (pinfunction "IREF_18") (pintype "input"))
    )
    (net (code "88") (name "Net-(U59-SCK)") (class "Default")
      (node (ref "R492") (pin "2") (pinfunction "2_2") (pintype "passive"))
      (node (ref "U59") (pin "5") (pinfunction "SCK_5") (pintype "input"))
    )
    (net (code "89") (name "Net-(U59-SDI)") (class "Default")
      (node (ref "R494") (pin "2") (pinfunction "2_2") (pintype "passive"))
      (node (ref "U59") (pin "6") (pinfunction "SDI_6") (pintype "input"))
    )
    (net (code "90") (name "Net-(U59-SDO)") (class "Default")
      (node (ref "R484") (pin "2") (pinfunction "2_2") (pintype "passive"))
      (node (ref "U59") (pin "7") (pinfunction "SDO_7") (pintype "output"))
    )
    (net (code "91") (name "Net-(U59-V18)") (class "Default")
      (node (ref "C379") (pin "2") (pinfunction "2_2") (pintype "passive"))
      (node (ref "U59") (pin "20") (pinfunction "V18_20") (pintype "power_in"))
    )
    (net (code "92") (name "Net-(U59-VCP)") (class "Default")
      (node (ref "C368") (pin "1") (pinfunction "1_1") (pintype "passive"))
      (node (ref "U59") (pin "24") (pinfunction "VCP_24") (pintype "power_in"))
    )
    (net (code "93") (name "Net-(U60-*CSB)") (class "Default")
      (node (ref "R493") (pin "2") (pinfunction "2_2") (pintype "passive"))
      (node (ref "U60") (pin "3") (pinfunction "*CSB_3") (pintype "input"))
    )
    (net (code "94") (name "Net-(U60-*FAULT)") (class "Default")
      (node (ref "R482") (pin "2") (pinfunction "2_2") (pintype "passive"))
      (node (ref "U60") (pin "1") (pinfunction "*FAULT_1") (pintype "output"))
    )
    (net (code "95") (name "Net-(U60-CFN)") (class "Default")
      (node (ref "C378") (pin "1") (pinfunction "1_1") (pintype "passive"))
      (node (ref "U60") (pin "22") (pinfunction "CFN_22") (pintype "power_in"))
    )
    (net (code "96") (name "Net-(U60-CFP)") (class "Default")
      (node (ref "C378") (pin "2") (pinfunction "2_2") (pintype "passive"))
      (node (ref "U60") (pin "23") (pinfunction "CFP_23") (pintype "power_in"))
    )
    (net (code "97") (name "Net-(U60-CMD)") (class "Default")
      (node (ref "R500") (pin "2") (pinfunction "2_2") (pintype "passive"))
      (node (ref "U60") (pin "2") (pinfunction "CMD_2") (pintype "input"))
    )
    (net (code "98") (name "Net-(U60-ENABLE)") (class "Default")
      (node (ref "R499") (pin "2") (pinfunction "2_2") (pintype "passive"))
      (node (ref "U60") (pin "21") (pinfunction "ENABLE_21") (pintype "input"))
    )
    (net (code "99") (name "Net-(U60-IREF)") (class "Default")
      (node (ref "R548") (pin "2") (pinfunction "2_2") (pintype "passive"))
      (node (ref "U60") (pin "18") (pinfunction "IREF_18") (pintype "input"))
    )
    (net (code "100") (name "Net-(U60-SCK)") (class "Default")
      (node (ref "R495") (pin "2") (pinfunction "2_2") (pintype "passive"))
      (node (ref "U60") (pin "5") (pinfunction "SCK_5") (pintype "input"))
    )
    (net (code "101") (name "Net-(U60-SDI)") (class "Default")
      (node (ref "R496") (pin "2") (pinfunction "2_2") (pintype "passive"))
      (node (ref "U60") (pin "6") (pinfunction "SDI_6") (pintype "input"))
    )
    (net (code "102") (name "Net-(U60-SDO)") (class "Default")
      (node (ref "R491") (pin "2") (pinfunction "2_2") (pintype "passive"))
      (node (ref "U60") (pin "7") (pinfunction "SDO_7") (pintype "output"))
    )
    (net (code "103") (name "Net-(U60-V18)") (class "Default")
      (node (ref "C380") (pin "2") (pinfunction "2_2") (pintype "passive"))
      (node (ref "U60") (pin "20") (pinfunction "V18_20") (pintype "power_in"))
    )
    (net (code "104") (name "Net-(U60-VCP)") (class "Default")
      (node (ref "C369") (pin "1") (pinfunction "1_1") (pintype "passive"))
      (node (ref "U60") (pin "24") (pinfunction "VCP_24") (pintype "power_in"))
    )
    (net (code "105") (name "Net-(U61-*CSB)") (class "Default")
      (node (ref "R568") (pin "2") (pinfunction "2_2") (pintype "passive"))
      (node (ref "U61") (pin "3") (pinfunction "*CSB_3") (pintype "input"))
    )
    (net (code "106") (name "Net-(U61-*FAULT)") (class "Default")
      (node (ref "R549") (pin "2") (pinfunction "2_2") (pintype "passive"))
      (node (ref "U61") (pin "1") (pinfunction "*FAULT_1") (pintype "output"))
    )
    (net (code "107") (name "Net-(U61-CFN)") (class "Default")
      (node (ref "C384") (pin "1") (pinfunction "1_1") (pintype "passive"))
      (node (ref "U61") (pin "22") (pinfunction "CFN_22") (pintype "power_in"))
    )
    (net (code "108") (name "Net-(U61-CFP)") (class "Default")
      (node (ref "C384") (pin "2") (pinfunction "2_2") (pintype "passive"))
      (node (ref "U61") (pin "23") (pinfunction "CFP_23") (pintype "power_in"))
    )
    (net (code "109") (name "Net-(U61-CMD)") (class "Default")
      (node (ref "R572") (pin "2") (pinfunction "2_2") (pintype "passive"))
      (node (ref "U61") (pin "2") (pinfunction "CMD_2") (pintype "input"))
    )
    (net (code "110") (name "Net-(U61-ENABLE)") (class "Default")
      (node (ref "R571") (pin "2") (pinfunction "2_2") (pintype "passive"))
      (node (ref "U61") (pin "21") (pinfunction "ENABLE_21") (pintype "input"))
    )
    (net (code "111") (name "Net-(U61-IREF)") (class "Default")
      (node (ref "R573") (pin "2") (pinfunction "2_2") (pintype "passive"))
      (node (ref "U61") (pin "18") (pinfunction "IREF_18") (pintype "input"))
    )
    (net (code "112") (name "Net-(U61-SCK)") (class "Default")
      (node (ref "R569") (pin "2") (pinfunction "2_2") (pintype "passive"))
      (node (ref "U61") (pin "5") (pinfunction "SCK_5") (pintype "input"))
    )
    (net (code "113") (name "Net-(U61-SDI)") (class "Default")
      (node (ref "R570") (pin "2") (pinfunction "2_2") (pintype "passive"))
      (node (ref "U61") (pin "6") (pinfunction "SDI_6") (pintype "input"))
    )
    (net (code "114") (name "Net-(U61-SDO)") (class "Default")
      (node (ref "R567") (pin "2") (pinfunction "2_2") (pintype "passive"))
      (node (ref "U61") (pin "7") (pinfunction "SDO_7") (pintype "output"))
    )
    (net (code "115") (name "Net-(U61-V18)") (class "Default")
      (node (ref "C385") (pin "2") (pinfunction "2_2") (pintype "passive"))
      (node (ref "U61") (pin "20") (pinfunction "V18_20") (pintype "power_in"))
    )
    (net (code "116") (name "Net-(U61-VCP)") (class "Default")
      (node (ref "C383") (pin "1") (pinfunction "1_1") (pintype "passive"))
      (node (ref "U61") (pin "24") (pinfunction "VCP_24") (pintype "power_in"))
    )
    (net (code "117") (name "unconnected-(U50-TRIGA-Pad8)") (class "Default")
      (node (ref "U50") (pin "8") (pinfunction "TRIGA_8") (pintype "input+no_connect"))
    )
    (net (code "118") (name "unconnected-(U50-TRIGB-Pad17)") (class "Default")
      (node (ref "U50") (pin "17") (pinfunction "TRIGB_17") (pintype "input+no_connect"))
    )
    (net (code "119") (name "unconnected-(U58-TRIGA-Pad8)") (class "Default")
      (node (ref "U58") (pin "8") (pinfunction "TRIGA_8") (pintype "input+no_connect"))
    )
    (net (code "120") (name "unconnected-(U58-TRIGB-Pad17)") (class "Default")
      (node (ref "U58") (pin "17") (pinfunction "TRIGB_17") (pintype "input+no_connect"))
    )
    (net (code "121") (name "unconnected-(U59-TRIGA-Pad8)") (class "Default")
      (node (ref "U59") (pin "8") (pinfunction "TRIGA_8") (pintype "input+no_connect"))
    )
    (net (code "122") (name "unconnected-(U59-TRIGB-Pad17)") (class "Default")
      (node (ref "U59") (pin "17") (pinfunction "TRIGB_17") (pintype "input+no_connect"))
    )
    (net (code "123") (name "unconnected-(U60-TRIGA-Pad8)") (class "Default")
      (node (ref "U60") (pin "8") (pinfunction "TRIGA_8") (pintype "input+no_connect"))
    )
    (net (code "124") (name "unconnected-(U60-TRIGB-Pad17)") (class "Default")
      (node (ref "U60") (pin "17") (pinfunction "TRIGB_17") (pintype "input+no_connect"))
    )
    (net (code "125") (name "unconnected-(U61-TRIGA-Pad8)") (class "Default")
      (node (ref "U61") (pin "8") (pinfunction "TRIGA_8") (pintype "input+no_connect"))
    )
    (net (code "126") (name "unconnected-(U61-TRIGB-Pad17)") (class "Default")
      (node (ref "U61") (pin "17") (pinfunction "TRIGB_17") (pintype "input+no_connect"))
    )
  )
)
